# GPS_Shield-v10.net
KiCad netlist of a schematic drawn in EAGLE
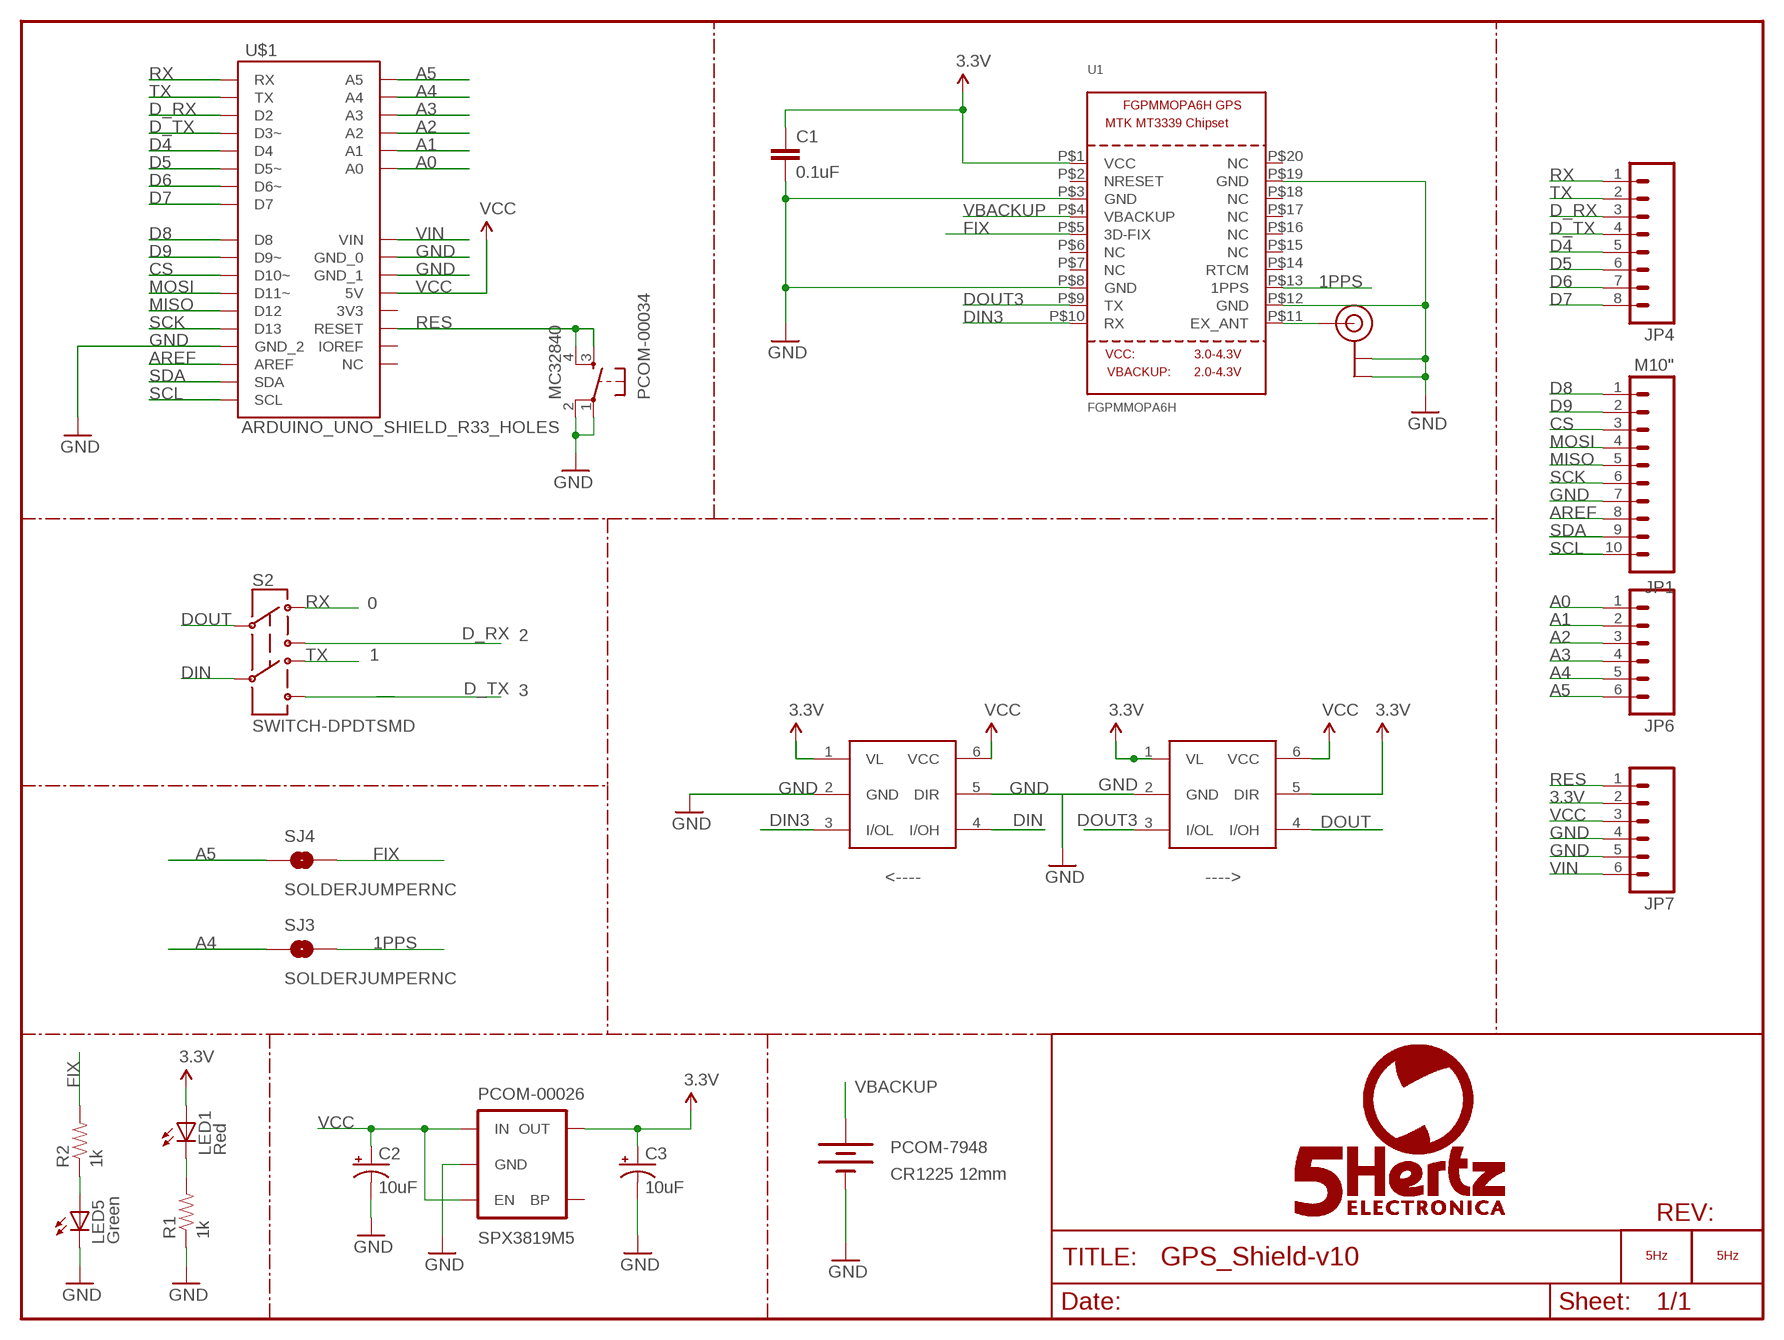
[diagram p0: schematic, sheet 1]

(export (version "E")
  (design (tool "Eeschema 10.0.6"))
  (components
    (comp (ref "C1")
      (value "0.1uF")
      (footprint "eagle-import:0603-CAP")
      (libsource (lib "eagle-import") (part "CAP0603-CAP"))
    )
    (comp (ref "C2")
      (value "10uF")
      (footprint "eagle-import:EIA3216")
      (libsource (lib "eagle-import") (part "CAP_POL1206"))
    )
    (comp (ref "C3")
      (value "10uF")
      (footprint "eagle-import:EIA3216")
      (libsource (lib "eagle-import") (part "CAP_POL1206"))
    )
    (comp (ref "JP1")
      (value "M10\"")
      (footprint "eagle-import:1X10")
      (libsource (lib "eagle-import") (part "M10{dblquote}"))
    )
    (comp (ref "JP4")
      (value "M08")
      (footprint "eagle-import:1X08")
      (libsource (lib "eagle-import") (part "M08"))
    )
    (comp (ref "JP6")
      (value "M06SIP")
      (footprint "eagle-import:1X06")
      (libsource (lib "eagle-import") (part "M06SIP"))
    )
    (comp (ref "JP7")
      (value "M06SIP")
      (footprint "eagle-import:1X06")
      (libsource (lib "eagle-import") (part "M06SIP"))
    )
    (comp (ref "LED1")
      (value "Red")
      (footprint "eagle-import:LED-0603")
      (libsource (lib "eagle-import") (part "LED0603"))
    )
    (comp (ref "LED5")
      (value "Green")
      (footprint "eagle-import:LED-0603")
      (libsource (lib "eagle-import") (part "LED0603"))
    )
    (comp (ref "LOGO1")
      (value "LOGO_5HZ_H_COOPER_15MM")
      (footprint "eagle-import:5HZ_LOGO_H_COOPER_15MM")
      (libsource (lib "eagle-import") (part "LOGO_5HZ_H_COOPER_15MM"))
    )
    (comp (ref "LOGO2")
      (value "LOGO_5HZ_H_20MM")
      (footprint "eagle-import:5HZ_LOGO_H_20MM")
      (libsource (lib "eagle-import") (part "LOGO_5HZ_H_20MM"))
    )
    (comp (ref "PCOM-00026")
      (value "SPX3819M5")
      (footprint "eagle-import:SOT23-5")
      (libsource (lib "eagle-import") (part "V_REG_LDOSMD"))
    )
    (comp (ref "PCOM-00034")
      (value "MC32840")
      (footprint "eagle-import:TACTILE_SWITCH_SMD")
      (libsource (lib "eagle-import") (part "TAC_SWITCHSMD"))
    )
    (comp (ref "PCOM-7948")
      (value "CR1225 12mm")
      (footprint "eagle-import:BATTCON_12MM_PTH")
      (libsource (lib "eagle-import") (part "BATTERY12PTH"))
    )
    (comp (ref "R1")
      (value "1k")
      (footprint "eagle-import:0603-RES")
      (libsource (lib "eagle-import") (part "RESISTOR0603-RES"))
    )
    (comp (ref "R2")
      (value "1k")
      (footprint "eagle-import:0603-RES")
      (libsource (lib "eagle-import") (part "RESISTOR0603-RES"))
    )
    (comp (ref "S2")
      (value "SWITCH-DPDTSMD")
      (footprint "eagle-import:AYZ0202")
      (libsource (lib "eagle-import") (part "SWITCH-DPDTSMD"))
    )
    (comp (ref "SJ3")
      (value "SOLDERJUMPERNC")
      (footprint "eagle-import:SJ_2S")
      (libsource (lib "eagle-import") (part "SOLDERJUMPERNC"))
    )
    (comp (ref "SJ4")
      (value "SOLDERJUMPERNC")
      (footprint "eagle-import:SJ_2S")
      (libsource (lib "eagle-import") (part "SOLDERJUMPERNC"))
    )
    (comp (ref "U$1")
      (value "ARDUINO_UNO_SHIELD_R33_HOLES")
      (footprint "eagle-import:UNO_R3_SHIELD_3_HOLES_NO_SILK")
      (libsource (lib "eagle-import") (part "ARDUINO_UNO_SHIELD_R33_HOLES"))
    )
    (comp (ref "U$7")
      (value "MAX337")
      (footprint "eagle-import:SOT-363")
      (libsource (lib "eagle-import") (part "MAX337"))
    )
    (comp (ref "U$8")
      (value "MAX337")
      (footprint "eagle-import:SOT-363")
      (libsource (lib "eagle-import") (part "MAX337"))
    )
    (comp (ref "U$20")
      (value "U.FL")
      (footprint "eagle-import:U.FL")
      (libsource (lib "eagle-import") (part "U.FL"))
    )
    (comp (ref "U1")
      (value "FGPMMOPA6H")
      (footprint "eagle-import:FGPMMOPA6H")
      (libsource (lib "eagle-import") (part "GPS_FGPMMOPA6H"))
    )
  )
  (nets
    (net (code "1") (name "/1PPS") (class "Default")
      (node (ref "SJ3") (pin "2") (pinfunction "2_2") (pintype "passive"))
      (node (ref "U1") (pin "P$13") (pinfunction "1PPS_P$13") (pintype "bidirectional"))
    )
    (net (code "2") (name "/A0") (class "Default")
      (node (ref "JP6") (pin "1") (pinfunction "1_1") (pintype "passive"))
      (node (ref "U$1") (pin "A0") (pinfunction "A0_A0") (pintype "bidirectional"))
    )
    (net (code "3") (name "/A1") (class "Default")
      (node (ref "JP6") (pin "2") (pinfunction "2_2") (pintype "passive"))
      (node (ref "U$1") (pin "A1") (pinfunction "A1_A1") (pintype "bidirectional"))
    )
    (net (code "4") (name "/A2") (class "Default")
      (node (ref "JP6") (pin "3") (pinfunction "3_3") (pintype "passive"))
      (node (ref "U$1") (pin "A2") (pinfunction "A2_A2") (pintype "bidirectional"))
    )
    (net (code "5") (name "/A3") (class "Default")
      (node (ref "JP6") (pin "4") (pinfunction "4_4") (pintype "passive"))
      (node (ref "U$1") (pin "A3") (pinfunction "A3_A3") (pintype "bidirectional"))
    )
    (net (code "6") (name "/A4") (class "Default")
      (node (ref "JP6") (pin "5") (pinfunction "5_5") (pintype "passive"))
      (node (ref "SJ3") (pin "1") (pinfunction "1_1") (pintype "passive"))
      (node (ref "U$1") (pin "A4") (pinfunction "A4_A4") (pintype "bidirectional"))
    )
    (net (code "7") (name "/A5") (class "Default")
      (node (ref "JP6") (pin "6") (pinfunction "6_6") (pintype "passive"))
      (node (ref "SJ4") (pin "1") (pinfunction "1_1") (pintype "passive"))
      (node (ref "U$1") (pin "A5") (pinfunction "A5_A5") (pintype "bidirectional"))
    )
    (net (code "8") (name "/AREF") (class "Default")
      (node (ref "JP1") (pin "8") (pinfunction "8_8") (pintype "passive"))
      (node (ref "U$1") (pin "AREF") (pinfunction "AREF_AREF") (pintype "bidirectional"))
    )
    (net (code "9") (name "/CS") (class "Default")
      (node (ref "JP1") (pin "3") (pinfunction "3_3") (pintype "passive"))
      (node (ref "U$1") (pin "D10") (pinfunction "D10~{}_D10") (pintype "bidirectional"))
    )
    (net (code "10") (name "/D4") (class "Default")
      (node (ref "JP4") (pin "5") (pinfunction "5_5") (pintype "passive"))
      (node (ref "U$1") (pin "D4") (pinfunction "D4_D4") (pintype "bidirectional"))
    )
    (net (code "11") (name "/D5") (class "Default")
      (node (ref "JP4") (pin "6") (pinfunction "6_6") (pintype "passive"))
      (node (ref "U$1") (pin "D5") (pinfunction "D5~{}_D5") (pintype "bidirectional"))
    )
    (net (code "12") (name "/D6") (class "Default")
      (node (ref "JP4") (pin "7") (pinfunction "7_7") (pintype "passive"))
      (node (ref "U$1") (pin "D6") (pinfunction "D6~{}_D6") (pintype "bidirectional"))
    )
    (net (code "13") (name "/D7") (class "Default")
      (node (ref "JP4") (pin "8") (pinfunction "8_8") (pintype "passive"))
      (node (ref "U$1") (pin "D7") (pinfunction "D7_D7") (pintype "bidirectional"))
    )
    (net (code "14") (name "/D8") (class "Default")
      (node (ref "JP1") (pin "1") (pinfunction "1_1") (pintype "passive"))
      (node (ref "U$1") (pin "D8") (pinfunction "D8_D8") (pintype "bidirectional"))
    )
    (net (code "15") (name "/D9") (class "Default")
      (node (ref "JP1") (pin "2") (pinfunction "2_2") (pintype "passive"))
      (node (ref "U$1") (pin "D9") (pinfunction "D9~{}_D9") (pintype "bidirectional"))
    )
    (net (code "16") (name "/DIN") (class "Default")
      (node (ref "S2") (pin "5") (pinfunction "5_5") (pintype "bidirectional"))
      (node (ref "U$7") (pin "4") (pinfunction "I/OH_4") (pintype "bidirectional"))
    )
    (net (code "17") (name "/DIN3") (class "Default")
      (node (ref "U$7") (pin "3") (pinfunction "I/OL_3") (pintype "bidirectional"))
      (node (ref "U1") (pin "P$10") (pinfunction "RX_P$10") (pintype "bidirectional"))
    )
    (net (code "18") (name "/DOUT") (class "Default")
      (node (ref "S2") (pin "2") (pinfunction "2_2") (pintype "bidirectional"))
      (node (ref "U$8") (pin "4") (pinfunction "I/OH_4") (pintype "bidirectional"))
    )
    (net (code "19") (name "/DOUT3") (class "Default")
      (node (ref "U$8") (pin "3") (pinfunction "I/OL_3") (pintype "bidirectional"))
      (node (ref "U1") (pin "P$9") (pinfunction "TX_P$9") (pintype "bidirectional"))
    )
    (net (code "20") (name "/D_RX") (class "Default")
      (node (ref "JP4") (pin "3") (pinfunction "3_3") (pintype "passive"))
      (node (ref "S2") (pin "3") (pinfunction "3_3") (pintype "bidirectional"))
      (node (ref "U$1") (pin "D2") (pinfunction "D2_D2") (pintype "bidirectional"))
    )
    (net (code "21") (name "/D_TX") (class "Default")
      (node (ref "JP4") (pin "4") (pinfunction "4_4") (pintype "passive"))
      (node (ref "S2") (pin "6") (pinfunction "6_6") (pintype "bidirectional"))
      (node (ref "U$1") (pin "D3") (pinfunction "D3~{}_D3") (pintype "bidirectional"))
    )
    (net (code "22") (name "/FIX") (class "Default")
      (node (ref "R2") (pin "2") (pinfunction "2_2") (pintype "passive"))
      (node (ref "SJ4") (pin "2") (pinfunction "2_2") (pintype "passive"))
      (node (ref "U1") (pin "P$5") (pinfunction "3D-FIX_P$5") (pintype "bidirectional"))
    )
    (net (code "23") (name "/MISO") (class "Default")
      (node (ref "JP1") (pin "5") (pinfunction "5_5") (pintype "passive"))
      (node (ref "U$1") (pin "D12") (pinfunction "D12_D12") (pintype "bidirectional"))
    )
    (net (code "24") (name "/MOSI") (class "Default")
      (node (ref "JP1") (pin "4") (pinfunction "4_4") (pintype "passive"))
      (node (ref "U$1") (pin "D11") (pinfunction "D11~{}_D11") (pintype "bidirectional"))
    )
    (net (code "25") (name "/RES") (class "Default")
      (node (ref "JP7") (pin "1") (pinfunction "1_1") (pintype "passive"))
      (node (ref "PCOM-00034") (pin "3") (pinfunction "3_3") (pintype "passive"))
      (node (ref "PCOM-00034") (pin "4") (pinfunction "4_4") (pintype "passive"))
      (node (ref "U$1") (pin "RES") (pinfunction "RESET_RES") (pintype "bidirectional"))
    )
    (net (code "26") (name "/RX") (class "Default")
      (node (ref "JP4") (pin "1") (pinfunction "1_1") (pintype "passive"))
      (node (ref "S2") (pin "1") (pinfunction "1_1") (pintype "bidirectional"))
      (node (ref "U$1") (pin "RX") (pinfunction "RX_RX") (pintype "bidirectional"))
    )
    (net (code "27") (name "/SCK") (class "Default")
      (node (ref "JP1") (pin "6") (pinfunction "6_6") (pintype "passive"))
      (node (ref "U$1") (pin "D13") (pinfunction "D13_D13") (pintype "bidirectional"))
    )
    (net (code "28") (name "/SCL") (class "Default")
      (node (ref "JP1") (pin "10") (pinfunction "10_10") (pintype "passive"))
      (node (ref "U$1") (pin "SCL") (pinfunction "SCL_SCL") (pintype "bidirectional"))
    )
    (net (code "29") (name "/SDA") (class "Default")
      (node (ref "JP1") (pin "9") (pinfunction "9_9") (pintype "passive"))
      (node (ref "U$1") (pin "SDA") (pinfunction "SDA_SDA") (pintype "bidirectional"))
    )
    (net (code "30") (name "/TX") (class "Default")
      (node (ref "JP4") (pin "2") (pinfunction "2_2") (pintype "passive"))
      (node (ref "S2") (pin "4") (pinfunction "4_4") (pintype "bidirectional"))
      (node (ref "U$1") (pin "TX") (pinfunction "TX_TX") (pintype "bidirectional"))
    )
    (net (code "31") (name "/VBACKUP") (class "Default")
      (node (ref "PCOM-7948") (pin "VCC@1") (pinfunction "+_VCC@1") (pintype "power_in"))
      (node (ref "U1") (pin "P$4") (pinfunction "VBACKUP_P$4") (pintype "bidirectional"))
    )
    (net (code "32") (name "/VIN") (class "Default")
      (node (ref "JP7") (pin "6") (pinfunction "6_6") (pintype "passive"))
      (node (ref "U$1") (pin "VIN") (pinfunction "VIN_VIN") (pintype "bidirectional"))
    )
    (net (code "33") (name "3.3V") (class "Default")
      (node (ref "C1") (pin "1") (pinfunction "1_1") (pintype "passive"))
      (node (ref "C3") (pin "A") (pinfunction "+_A") (pintype "passive"))
      (node (ref "JP7") (pin "2") (pinfunction "2_2") (pintype "passive"))
      (node (ref "LED1") (pin "A") (pinfunction "A_A") (pintype "passive"))
      (node (ref "PCOM-00026") (pin "5") (pinfunction "OUT_5") (pintype "passive"))
      (node (ref "U$7") (pin "1") (pinfunction "VL_1") (pintype "bidirectional"))
      (node (ref "U$8") (pin "1") (pinfunction "VL_1") (pintype "bidirectional"))
      (node (ref "U$8") (pin "5") (pinfunction "DIR_5") (pintype "bidirectional"))
      (node (ref "U1") (pin "P$1") (pinfunction "VCC_P$1") (pintype "bidirectional"))
    )
    (net (code "34") (name "GND") (class "Default")
      (node (ref "C1") (pin "2") (pinfunction "2_2") (pintype "passive"))
      (node (ref "C2") (pin "C") (pinfunction "-_C") (pintype "passive"))
      (node (ref "C3") (pin "C") (pinfunction "-_C") (pintype "passive"))
      (node (ref "JP1") (pin "7") (pinfunction "7_7") (pintype "passive"))
      (node (ref "JP7") (pin "4") (pinfunction "4_4") (pintype "passive"))
      (node (ref "JP7") (pin "5") (pinfunction "5_5") (pintype "passive"))
      (node (ref "LED5") (pin "C") (pinfunction "C_C") (pintype "passive"))
      (node (ref "PCOM-00026") (pin "2") (pinfunction "GND_2") (pintype "input"))
      (node (ref "PCOM-00034") (pin "1") (pinfunction "1_1") (pintype "passive"))
      (node (ref "PCOM-00034") (pin "2") (pinfunction "2_2") (pintype "passive"))
      (node (ref "PCOM-7948") (pin "GND") (pinfunction "-_GND") (pintype "power_in"))
      (node (ref "R1") (pin "1") (pinfunction "1_1") (pintype "passive"))
      (node (ref "U$1") (pin "GND_0") (pinfunction "GND_0_GND_0") (pintype "bidirectional"))
      (node (ref "U$1") (pin "GND_1") (pinfunction "GND_1_GND_1") (pintype "bidirectional"))
      (node (ref "U$1") (pin "GND_2") (pinfunction "GND_2_GND_2") (pintype "bidirectional"))
      (node (ref "U$20") (pin "P$1") (pinfunction "GND_P$1") (pintype "bidirectional"))
      (node (ref "U$20") (pin "P$2") (pinfunction "GND_P$2") (pintype "bidirectional"))
      (node (ref "U$7") (pin "2") (pinfunction "GND_2") (pintype "bidirectional"))
      (node (ref "U$7") (pin "5") (pinfunction "DIR_5") (pintype "bidirectional"))
      (node (ref "U$8") (pin "2") (pinfunction "GND_2") (pintype "bidirectional"))
      (node (ref "U1") (pin "P$12") (pinfunction "GND_P$12") (pintype "bidirectional"))
      (node (ref "U1") (pin "P$19") (pinfunction "GND_P$19") (pintype "bidirectional"))
      (node (ref "U1") (pin "P$3") (pinfunction "GND_P$3") (pintype "bidirectional"))
      (node (ref "U1") (pin "P$8") (pinfunction "GND_P$8") (pintype "bidirectional"))
    )
    (net (code "35") (name "Net-(LED1-PadC)") (class "Default")
      (node (ref "LED1") (pin "C") (pinfunction "C_C") (pintype "passive"))
      (node (ref "R1") (pin "2") (pinfunction "2_2") (pintype "passive"))
    )
    (net (code "36") (name "Net-(LED5-PadA)") (class "Default")
      (node (ref "LED5") (pin "A") (pinfunction "A_A") (pintype "passive"))
      (node (ref "R2") (pin "1") (pinfunction "1_1") (pintype "passive"))
    )
    (net (code "37") (name "Net-(U$20-SIGNAL)") (class "Default")
      (node (ref "U$20") (pin "P$3") (pinfunction "SIGNAL_P$3") (pintype "bidirectional"))
      (node (ref "U1") (pin "P$11") (pinfunction "EX_ANT_P$11") (pintype "bidirectional"))
    )
    (net (code "38") (name "VCC") (class "Default")
      (node (ref "C2") (pin "A") (pinfunction "+_A") (pintype "passive"))
      (node (ref "JP7") (pin "3") (pinfunction "3_3") (pintype "passive"))
      (node (ref "PCOM-00026") (pin "1") (pinfunction "IN_1") (pintype "input"))
      (node (ref "PCOM-00026") (pin "3") (pinfunction "EN_3") (pintype "input"))
      (node (ref "U$1") (pin "5V") (pinfunction "5V_5V") (pintype "bidirectional"))
      (node (ref "U$7") (pin "6") (pinfunction "VCC_6") (pintype "bidirectional"))
      (node (ref "U$8") (pin "6") (pinfunction "VCC_6") (pintype "bidirectional"))
    )
    (net (code "39") (name "unconnected-(PCOM-00026-BP-Pad4)") (class "Default")
      (node (ref "PCOM-00026") (pin "4") (pinfunction "BP_4") (pintype "input"))
    )
    (net (code "40") (name "unconnected-(U$1-3V3-Pad3.3V)") (class "Default")
      (node (ref "U$1") (pin "3.3V") (pinfunction "3V3_3.3V") (pintype "bidirectional"))
    )
    (net (code "41") (name "unconnected-(U$1-PadIOREF)") (class "Default")
      (node (ref "U$1") (pin "IOREF") (pinfunction "IOREF_IOREF") (pintype "bidirectional"))
    )
    (net (code "42") (name "unconnected-(U$1-PadNC)") (class "Default")
      (node (ref "U$1") (pin "NC") (pinfunction "NC_NC") (pintype "no_connect"))
    )
    (net (code "43") (name "unconnected-(U1-NC-PadP$6)") (class "Default")
      (node (ref "U1") (pin "P$6") (pinfunction "NC_P$6") (pintype "bidirectional"))
    )
    (net (code "44") (name "unconnected-(U1-NC-PadP$7)") (class "Default")
      (node (ref "U1") (pin "P$7") (pinfunction "NC_P$7") (pintype "bidirectional"))
    )
    (net (code "45") (name "unconnected-(U1-NC-PadP$15)") (class "Default")
      (node (ref "U1") (pin "P$15") (pinfunction "NC_P$15") (pintype "bidirectional"))
    )
    (net (code "46") (name "unconnected-(U1-NC-PadP$16)") (class "Default")
      (node (ref "U1") (pin "P$16") (pinfunction "NC_P$16") (pintype "bidirectional"))
    )
    (net (code "47") (name "unconnected-(U1-NC-PadP$17)") (class "Default")
      (node (ref "U1") (pin "P$17") (pinfunction "NC_P$17") (pintype "bidirectional"))
    )
    (net (code "48") (name "unconnected-(U1-NC-PadP$18)") (class "Default")
      (node (ref "U1") (pin "P$18") (pinfunction "NC_P$18") (pintype "bidirectional"))
    )
    (net (code "49") (name "unconnected-(U1-NC-PadP$20)") (class "Default")
      (node (ref "U1") (pin "P$20") (pinfunction "NC_P$20") (pintype "bidirectional"))
    )
    (net (code "50") (name "unconnected-(U1-NRESET-PadP$2)") (class "Default")
      (node (ref "U1") (pin "P$2") (pinfunction "NRESET_P$2") (pintype "bidirectional"))
    )
    (net (code "51") (name "unconnected-(U1-RTCM-PadP$14)") (class "Default")
      (node (ref "U1") (pin "P$14") (pinfunction "RTCM_P$14") (pintype "bidirectional"))
    )
  )
)
